# Placa_do_filtro_notch.net
KiCad netlist of a schematic drawn in EAGLE
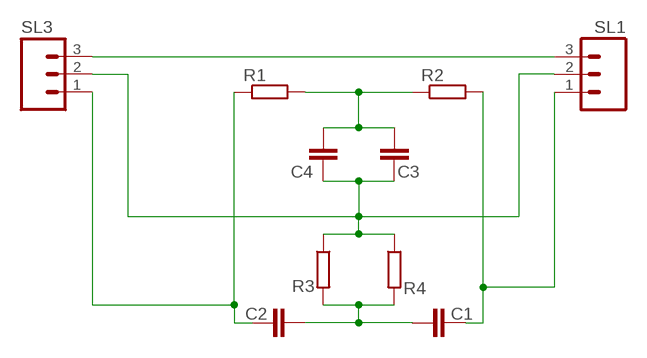
[diagram p0: schematic, sheet 1]

(export (version "E")
  (design (tool "Eeschema 10.0.6"))
  (components
    (comp (ref "C1")
      (value "C-EUC0805")
      (footprint "eagle-import:C0805")
      (fields (field (name "SPICEPREFIX") "C"))
      (libsource (lib "eagle-import") (part "C-EUC0805"))
    )
    (comp (ref "C2")
      (value "C-EUC0805")
      (footprint "eagle-import:C0805")
      (fields (field (name "SPICEPREFIX") "C"))
      (libsource (lib "eagle-import") (part "C-EUC0805"))
    )
    (comp (ref "C3")
      (value "C-EUC0805")
      (footprint "eagle-import:C0805")
      (fields (field (name "SPICEPREFIX") "C"))
      (libsource (lib "eagle-import") (part "C-EUC0805"))
    )
    (comp (ref "C4")
      (value "C-EUC0805")
      (footprint "eagle-import:C0805")
      (fields (field (name "SPICEPREFIX") "C"))
      (libsource (lib "eagle-import") (part "C-EUC0805"))
    )
    (comp (ref "R1")
      (value "R-EU_R0805")
      (footprint "eagle-import:R0805")
      (fields (field (name "SPICEPREFIX") "R"))
      (libsource (lib "eagle-import") (part "R-EU_R0805"))
    )
    (comp (ref "R2")
      (value "R-EU_R0805")
      (footprint "eagle-import:R0805")
      (fields (field (name "SPICEPREFIX") "R"))
      (libsource (lib "eagle-import") (part "R-EU_R0805"))
    )
    (comp (ref "R3")
      (value "R-EU_R0805")
      (footprint "eagle-import:R0805")
      (fields (field (name "SPICEPREFIX") "R"))
      (libsource (lib "eagle-import") (part "R-EU_R0805"))
    )
    (comp (ref "R4")
      (value "R-EU_R0805")
      (footprint "eagle-import:R0805")
      (fields (field (name "SPICEPREFIX") "R"))
      (libsource (lib "eagle-import") (part "R-EU_R0805"))
    )
    (comp (ref "SL1")
      (value "M03")
      (footprint "eagle-import:03P")
      (fields (field (name "SPICEPREFIX") "U"))
      (libsource (lib "eagle-import") (part "M03"))
    )
    (comp (ref "SL3")
      (value "M03")
      (footprint "eagle-import:03P")
      (fields (field (name "SPICEPREFIX") "J"))
      (libsource (lib "eagle-import") (part "M03"))
    )
  )
  (nets
    (net (code "1") (name "Net-(C1-Pad1)") (class "Default")
      (node (ref "C1") (pin "1") (pinfunction "1_1") (pintype "passive"))
      (node (ref "R2") (pin "2") (pinfunction "2_2") (pintype "passive"))
      (node (ref "SL1") (pin "1") (pinfunction "1_1") (pintype "passive"))
    )
    (net (code "2") (name "Net-(C1-Pad2)") (class "Default")
      (node (ref "C1") (pin "2") (pinfunction "2_2") (pintype "passive"))
      (node (ref "C2") (pin "2") (pinfunction "2_2") (pintype "passive"))
      (node (ref "R3") (pin "2") (pinfunction "2_2") (pintype "passive"))
      (node (ref "R4") (pin "2") (pinfunction "2_2") (pintype "passive"))
    )
    (net (code "3") (name "Net-(C2-Pad1)") (class "Default")
      (node (ref "C2") (pin "1") (pinfunction "1_1") (pintype "passive"))
      (node (ref "R1") (pin "1") (pinfunction "1_1") (pintype "passive"))
      (node (ref "SL3") (pin "1") (pinfunction "1_1") (pintype "passive"))
    )
    (net (code "4") (name "Net-(C3-Pad1)") (class "Default")
      (node (ref "C3") (pin "1") (pinfunction "1_1") (pintype "passive"))
      (node (ref "C4") (pin "1") (pinfunction "1_1") (pintype "passive"))
      (node (ref "R3") (pin "1") (pinfunction "1_1") (pintype "passive"))
      (node (ref "R4") (pin "1") (pinfunction "1_1") (pintype "passive"))
      (node (ref "SL1") (pin "2") (pinfunction "2_2") (pintype "passive"))
      (node (ref "SL3") (pin "2") (pinfunction "2_2") (pintype "passive"))
    )
    (net (code "5") (name "Net-(C3-Pad2)") (class "Default")
      (node (ref "C3") (pin "2") (pinfunction "2_2") (pintype "passive"))
      (node (ref "C4") (pin "2") (pinfunction "2_2") (pintype "passive"))
      (node (ref "R1") (pin "2") (pinfunction "2_2") (pintype "passive"))
      (node (ref "R2") (pin "1") (pinfunction "1_1") (pintype "passive"))
    )
    (net (code "6") (name "Net-(SL1-Pad3)") (class "Default")
      (node (ref "SL1") (pin "3") (pinfunction "3_3") (pintype "passive"))
      (node (ref "SL3") (pin "3") (pinfunction "3_3") (pintype "passive"))
    )
  )
)
